# Main.net
KiCad netlist of a schematic drawn in Altium Designer
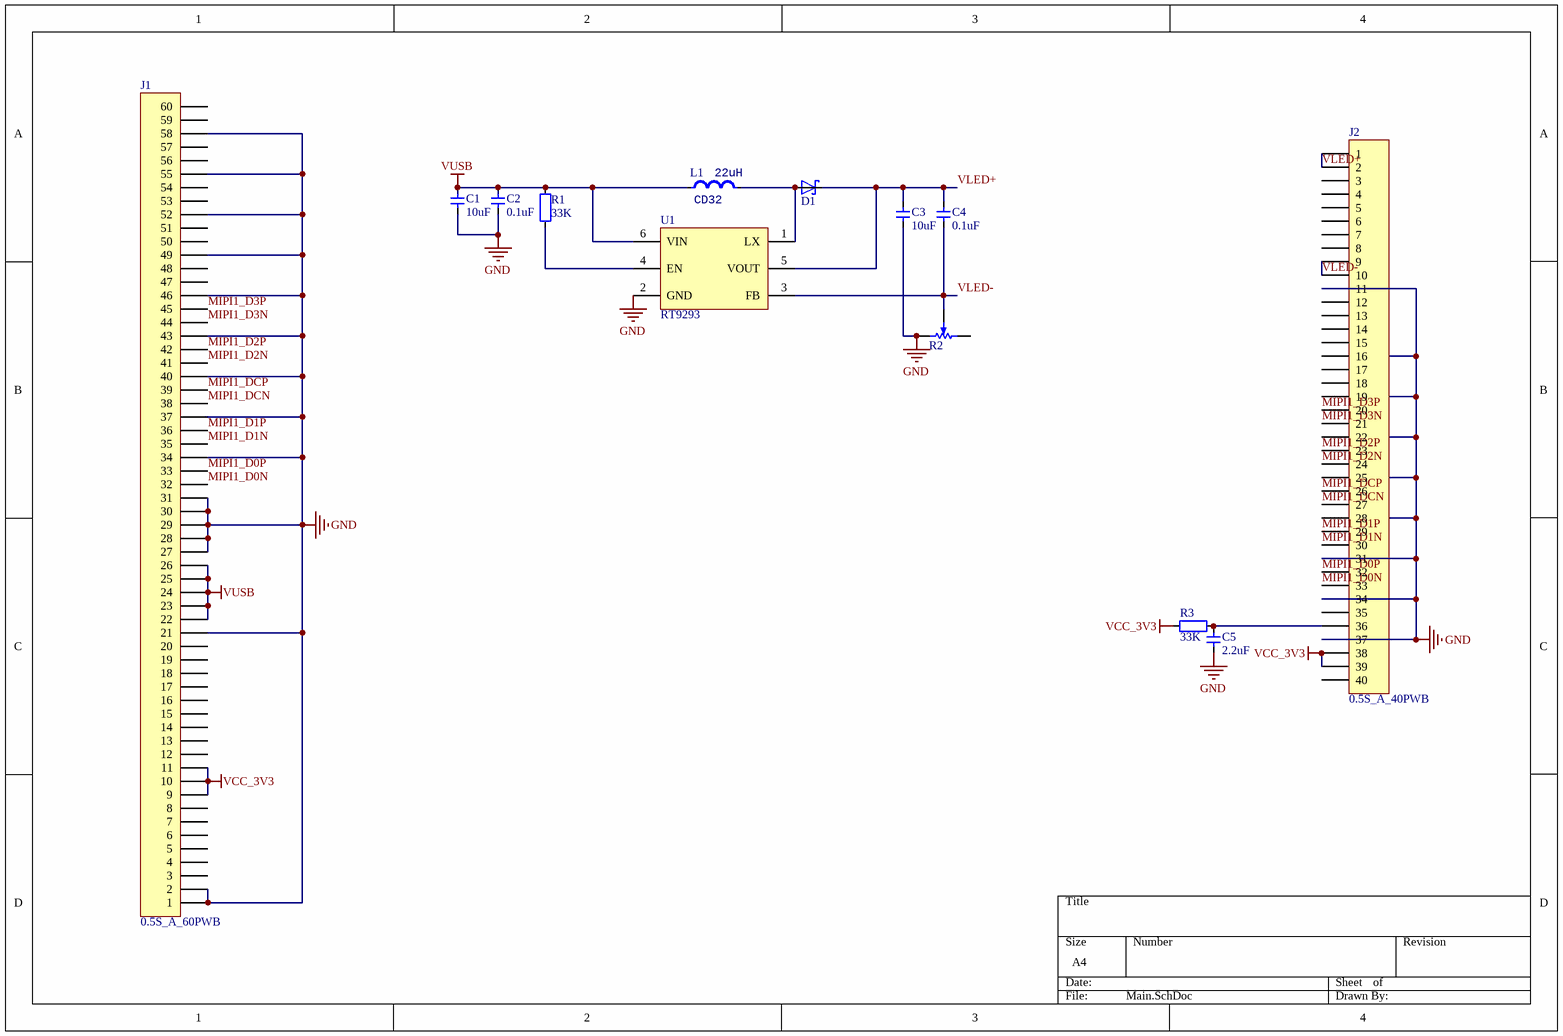
[diagram p0: Main.SchDoc]

(export (version "E")
  (design (tool "Eeschema 10.0.6"))
  (components
    (comp (ref "C1")
      (value "10uF")
      (footprint "CAP_0402")
      (description "Capacitor")
      (libsource (lib "MyPcbLib") (part "电容-0402"))
    )
    (comp (ref "C2")
      (value "0.1uF")
      (footprint "CAP_0402")
      (description "Capacitor")
      (libsource (lib "MyPcbLib") (part "电容-0402"))
    )
    (comp (ref "C3")
      (value "10uF")
      (footprint "CAP_0402")
      (description "Capacitor")
      (libsource (lib "MyPcbLib") (part "电容-0402"))
    )
    (comp (ref "C4")
      (value "0.1uF")
      (footprint "CAP_0402")
      (description "Capacitor")
      (libsource (lib "MyPcbLib") (part "电容-0402"))
    )
    (comp (ref "C5")
      (value "2.2uF")
      (footprint "CAP_0402")
      (description "Capacitor")
      (libsource (lib "MyPcbLib") (part "电容-0402"))
    )
    (comp (ref "D1")
      (value "RSX501L-20")
      (footprint "mLib:DO-214")
      (description "Diode Schottky 40V 1A Surface Mount SMA _DO-214AC_")
      (fields (field (name "MP") "SS14") (field (name "MF") "ON Semiconductor"))
      (libsource (lib "mLib") (part "RSX501L-20"))
    )
    (comp (ref "J1")
      (value "0.5S_A_60PWB")
      (footprint "FFC_0.5_60")
      (description "Header, 60-Pin")
      (fields (field (name "PUBLISHER") "Altium Limited"))
      (libsource (lib "mLib") (part "FPC60-0.5mm"))
    )
    (comp (ref "J2")
      (value "0.5S_A_40PWB")
      (footprint "FFC_0.5_40")
      (description "Header, 40-Pin")
      (fields (field (name "PUBLISHER") "Altium Limited"))
      (libsource (lib "MyPcbLib") (part "FPC40-0.5mm"))
    )
    (comp (ref "L1")
      (value "22uH")
      (footprint "IND_CD32")
      (description "Inductor")
      (fields (field (name "TYPE") "CD32") (field (name "Comment") "CD32"))
      (libsource (lib "KitSprout") (part "Ind_CD32"))
    )
    (comp (ref "R1")
      (value "33K")
      (footprint "RES_0402")
      (description "Resistor")
      (libsource (lib "MyPcbLib") (part "电阻-0402"))
    )
    (comp (ref "R2")
      (value "电位器-贴片")
      (footprint "贴片电位器 3*3")
      (fields (field (name "PUBLISHER") "Altium Limited"))
      (libsource (lib "MyPcbLib") (part "电位器-贴片"))
    )
    (comp (ref "R3")
      (value "33K")
      (footprint "RES_0402")
      (description "Resistor")
      (libsource (lib "") (part "电阻-0402_1"))
    )
    (comp (ref "U1")
      (value "RT9293")
      (footprint "SOT23-6")
      (description "LCD-LED Driver")
      (libsource (lib "mLib") (part "RT9293"))
    )
  )
  (nets
    (net (code "1") (name "/MIPI1_D0N") (class "Default")
      (node (ref "J1") (pin "32") (pinfunction "32_32") (pintype "passive"))
      (node (ref "J2") (pin "33") (pinfunction "33_33") (pintype "passive"))
    )
    (net (code "2") (name "/MIPI1_D0P") (class "Default")
      (node (ref "J1") (pin "33") (pinfunction "33_33") (pintype "passive"))
      (node (ref "J2") (pin "32") (pinfunction "32_32") (pintype "passive"))
    )
    (net (code "3") (name "/MIPI1_D1N") (class "Default")
      (node (ref "J1") (pin "35") (pinfunction "35_35") (pintype "passive"))
      (node (ref "J2") (pin "30") (pinfunction "30_30") (pintype "passive"))
    )
    (net (code "4") (name "/MIPI1_D1P") (class "Default")
      (node (ref "J1") (pin "36") (pinfunction "36_36") (pintype "passive"))
      (node (ref "J2") (pin "29") (pinfunction "29_29") (pintype "passive"))
    )
    (net (code "5") (name "/MIPI1_D2N") (class "Default")
      (node (ref "J1") (pin "41") (pinfunction "41_41") (pintype "passive"))
      (node (ref "J2") (pin "24") (pinfunction "24_24") (pintype "passive"))
    )
    (net (code "6") (name "/MIPI1_D2P") (class "Default")
      (node (ref "J1") (pin "42") (pinfunction "42_42") (pintype "passive"))
      (node (ref "J2") (pin "23") (pinfunction "23_23") (pintype "passive"))
    )
    (net (code "7") (name "/MIPI1_D3N") (class "Default")
      (node (ref "J1") (pin "44") (pinfunction "44_44") (pintype "passive"))
      (node (ref "J2") (pin "21") (pinfunction "21_21") (pintype "passive"))
    )
    (net (code "8") (name "/MIPI1_D3P") (class "Default")
      (node (ref "J1") (pin "45") (pinfunction "45_45") (pintype "passive"))
      (node (ref "J2") (pin "20") (pinfunction "20_20") (pintype "passive"))
    )
    (net (code "9") (name "/MIPI1_DCN") (class "Default")
      (node (ref "J1") (pin "38") (pinfunction "38_38") (pintype "passive"))
      (node (ref "J2") (pin "27") (pinfunction "27_27") (pintype "passive"))
    )
    (net (code "10") (name "/MIPI1_DCP") (class "Default")
      (node (ref "J1") (pin "39") (pinfunction "39_39") (pintype "passive"))
      (node (ref "J2") (pin "26") (pinfunction "26_26") (pintype "passive"))
    )
    (net (code "11") (name "/VLED+") (class "Default")
      (node (ref "C3") (pin "2") (pinfunction "2_2") (pintype "passive"))
      (node (ref "C4") (pin "2") (pinfunction "2_2") (pintype "passive"))
      (node (ref "D1") (pin "1") (pinfunction "1_1") (pintype "passive"))
      (node (ref "J2") (pin "1") (pinfunction "1_1") (pintype "passive"))
      (node (ref "J2") (pin "2") (pinfunction "2_2") (pintype "passive"))
      (node (ref "U1") (pin "5") (pinfunction "VOUT_5") (pintype "passive"))
    )
    (net (code "12") (name "/VLED-") (class "Default")
      (node (ref "C4") (pin "1") (pinfunction "1_1") (pintype "passive"))
      (node (ref "J2") (pin "10") (pinfunction "10_10") (pintype "passive"))
      (node (ref "J2") (pin "9") (pinfunction "9_9") (pintype "passive"))
      (node (ref "R2") (pin "3") (pinfunction "W_3") (pintype "passive"))
      (node (ref "U1") (pin "3") (pinfunction "FB_3") (pintype "passive"))
    )
    (net (code "13") (name "GND") (class "Default")
      (node (ref "C1") (pin "1") (pinfunction "1_1") (pintype "passive"))
      (node (ref "C2") (pin "1") (pinfunction "1_1") (pintype "passive"))
      (node (ref "C3") (pin "1") (pinfunction "1_1") (pintype "passive"))
      (node (ref "C5") (pin "2") (pinfunction "2_2") (pintype "passive"))
      (node (ref "J1") (pin "1") (pinfunction "1_1") (pintype "passive"))
      (node (ref "J1") (pin "2") (pinfunction "2_2") (pintype "passive"))
      (node (ref "J1") (pin "21") (pinfunction "21_21") (pintype "passive"))
      (node (ref "J1") (pin "27") (pinfunction "27_27") (pintype "passive"))
      (node (ref "J1") (pin "28") (pinfunction "28_28") (pintype "passive"))
      (node (ref "J1") (pin "29") (pinfunction "29_29") (pintype "passive"))
      (node (ref "J1") (pin "30") (pinfunction "30_30") (pintype "passive"))
      (node (ref "J1") (pin "31") (pinfunction "31_31") (pintype "passive"))
      (node (ref "J1") (pin "34") (pinfunction "34_34") (pintype "passive"))
      (node (ref "J1") (pin "37") (pinfunction "37_37") (pintype "passive"))
      (node (ref "J1") (pin "40") (pinfunction "40_40") (pintype "passive"))
      (node (ref "J1") (pin "43") (pinfunction "43_43") (pintype "passive"))
      (node (ref "J1") (pin "46") (pinfunction "46_46") (pintype "passive"))
      (node (ref "J1") (pin "49") (pinfunction "49_49") (pintype "passive"))
      (node (ref "J1") (pin "52") (pinfunction "52_52") (pintype "passive"))
      (node (ref "J1") (pin "55") (pinfunction "55_55") (pintype "passive"))
      (node (ref "J1") (pin "58") (pinfunction "58_58") (pintype "passive"))
      (node (ref "J2") (pin "11") (pinfunction "11_11") (pintype "passive"))
      (node (ref "J2") (pin "16") (pinfunction "16_16") (pintype "passive"))
      (node (ref "J2") (pin "19") (pinfunction "19_19") (pintype "passive"))
      (node (ref "J2") (pin "22") (pinfunction "22_22") (pintype "passive"))
      (node (ref "J2") (pin "25") (pinfunction "25_25") (pintype "passive"))
      (node (ref "J2") (pin "28") (pinfunction "28_28") (pintype "passive"))
      (node (ref "J2") (pin "31") (pinfunction "31_31") (pintype "passive"))
      (node (ref "J2") (pin "34") (pinfunction "34_34") (pintype "passive"))
      (node (ref "J2") (pin "37") (pinfunction "37_37") (pintype "passive"))
      (node (ref "R2") (pin "1") (pinfunction "+_1") (pintype "passive"))
      (node (ref "U1") (pin "2") (pinfunction "GND_2") (pintype "passive"))
    )
    (net (code "14") (name "Net-(C5-Pad1)") (class "Default")
      (node (ref "C5") (pin "1") (pinfunction "1_1") (pintype "passive"))
      (node (ref "J2") (pin "36") (pinfunction "36_36") (pintype "passive"))
      (node (ref "R3") (pin "1") (pinfunction "1_1") (pintype "passive"))
    )
    (net (code "15") (name "Net-(U1-EN)") (class "Default")
      (node (ref "R1") (pin "1") (pinfunction "1_1") (pintype "passive"))
      (node (ref "U1") (pin "4") (pinfunction "EN_4") (pintype "passive"))
    )
    (net (code "16") (name "Net-(U1-LX)") (class "Default")
      (node (ref "D1") (pin "2") (pinfunction "2_2") (pintype "passive"))
      (node (ref "L1") (pin "2") (pinfunction "2_2") (pintype "passive"))
      (node (ref "U1") (pin "1") (pinfunction "LX_1") (pintype "passive"))
    )
    (net (code "17") (name "VCC_3V3") (class "Default")
      (node (ref "J1") (pin "10") (pinfunction "10_10") (pintype "passive"))
      (node (ref "J1") (pin "11") (pinfunction "11_11") (pintype "passive"))
      (node (ref "J1") (pin "9") (pinfunction "9_9") (pintype "passive"))
      (node (ref "J2") (pin "38") (pinfunction "38_38") (pintype "passive"))
      (node (ref "J2") (pin "39") (pinfunction "39_39") (pintype "passive"))
      (node (ref "R3") (pin "2") (pinfunction "2_2") (pintype "passive"))
    )
    (net (code "18") (name "VUSB") (class "Default")
      (node (ref "C1") (pin "2") (pinfunction "2_2") (pintype "passive"))
      (node (ref "C2") (pin "2") (pinfunction "2_2") (pintype "passive"))
      (node (ref "J1") (pin "22") (pinfunction "22_22") (pintype "passive"))
      (node (ref "J1") (pin "23") (pinfunction "23_23") (pintype "passive"))
      (node (ref "J1") (pin "24") (pinfunction "24_24") (pintype "passive"))
      (node (ref "J1") (pin "25") (pinfunction "25_25") (pintype "passive"))
      (node (ref "J1") (pin "26") (pinfunction "26_26") (pintype "passive"))
      (node (ref "L1") (pin "1") (pinfunction "1_1") (pintype "passive"))
      (node (ref "R1") (pin "2") (pinfunction "2_2") (pintype "passive"))
      (node (ref "U1") (pin "6") (pinfunction "VIN_6") (pintype "passive"))
    )
    (net (code "19") (name "unconnected-(J1-Pad3)") (class "Default")
      (node (ref "J1") (pin "3") (pinfunction "3_3") (pintype "passive"))
    )
    (net (code "20") (name "unconnected-(J1-Pad4)") (class "Default")
      (node (ref "J1") (pin "4") (pinfunction "4_4") (pintype "passive"))
    )
    (net (code "21") (name "unconnected-(J1-Pad5)") (class "Default")
      (node (ref "J1") (pin "5") (pinfunction "5_5") (pintype "passive"))
    )
    (net (code "22") (name "unconnected-(J1-Pad6)") (class "Default")
      (node (ref "J1") (pin "6") (pinfunction "6_6") (pintype "passive"))
    )
    (net (code "23") (name "unconnected-(J1-Pad7)") (class "Default")
      (node (ref "J1") (pin "7") (pinfunction "7_7") (pintype "passive"))
    )
    (net (code "24") (name "unconnected-(J1-Pad8)") (class "Default")
      (node (ref "J1") (pin "8") (pinfunction "8_8") (pintype "passive"))
    )
    (net (code "25") (name "unconnected-(J1-Pad12)") (class "Default")
      (node (ref "J1") (pin "12") (pinfunction "12_12") (pintype "passive"))
    )
    (net (code "26") (name "unconnected-(J1-Pad13)") (class "Default")
      (node (ref "J1") (pin "13") (pinfunction "13_13") (pintype "passive"))
    )
    (net (code "27") (name "unconnected-(J1-Pad14)") (class "Default")
      (node (ref "J1") (pin "14") (pinfunction "14_14") (pintype "passive"))
    )
    (net (code "28") (name "unconnected-(J1-Pad15)") (class "Default")
      (node (ref "J1") (pin "15") (pinfunction "15_15") (pintype "passive"))
    )
    (net (code "29") (name "unconnected-(J1-Pad16)") (class "Default")
      (node (ref "J1") (pin "16") (pinfunction "16_16") (pintype "passive"))
    )
    (net (code "30") (name "unconnected-(J1-Pad17)") (class "Default")
      (node (ref "J1") (pin "17") (pinfunction "17_17") (pintype "passive"))
    )
    (net (code "31") (name "unconnected-(J1-Pad18)") (class "Default")
      (node (ref "J1") (pin "18") (pinfunction "18_18") (pintype "passive"))
    )
    (net (code "32") (name "unconnected-(J1-Pad19)") (class "Default")
      (node (ref "J1") (pin "19") (pinfunction "19_19") (pintype "passive"))
    )
    (net (code "33") (name "unconnected-(J1-Pad20)") (class "Default")
      (node (ref "J1") (pin "20") (pinfunction "20_20") (pintype "passive"))
    )
    (net (code "34") (name "unconnected-(J1-Pad47)") (class "Default")
      (node (ref "J1") (pin "47") (pinfunction "47_47") (pintype "passive"))
    )
    (net (code "35") (name "unconnected-(J1-Pad48)") (class "Default")
      (node (ref "J1") (pin "48") (pinfunction "48_48") (pintype "passive"))
    )
    (net (code "36") (name "unconnected-(J1-Pad50)") (class "Default")
      (node (ref "J1") (pin "50") (pinfunction "50_50") (pintype "passive"))
    )
    (net (code "37") (name "unconnected-(J1-Pad51)") (class "Default")
      (node (ref "J1") (pin "51") (pinfunction "51_51") (pintype "passive"))
    )
    (net (code "38") (name "unconnected-(J1-Pad53)") (class "Default")
      (node (ref "J1") (pin "53") (pinfunction "53_53") (pintype "passive"))
    )
    (net (code "39") (name "unconnected-(J1-Pad54)") (class "Default")
      (node (ref "J1") (pin "54") (pinfunction "54_54") (pintype "passive"))
    )
    (net (code "40") (name "unconnected-(J1-Pad56)") (class "Default")
      (node (ref "J1") (pin "56") (pinfunction "56_56") (pintype "passive"))
    )
    (net (code "41") (name "unconnected-(J1-Pad57)") (class "Default")
      (node (ref "J1") (pin "57") (pinfunction "57_57") (pintype "passive"))
    )
    (net (code "42") (name "unconnected-(J1-Pad59)") (class "Default")
      (node (ref "J1") (pin "59") (pinfunction "59_59") (pintype "passive"))
    )
    (net (code "43") (name "unconnected-(J1-Pad60)") (class "Default")
      (node (ref "J1") (pin "60") (pinfunction "60_60") (pintype "passive"))
    )
    (net (code "44") (name "unconnected-(J2-Pad3)") (class "Default")
      (node (ref "J2") (pin "3") (pinfunction "3_3") (pintype "passive"))
    )
    (net (code "45") (name "unconnected-(J2-Pad4)") (class "Default")
      (node (ref "J2") (pin "4") (pinfunction "4_4") (pintype "passive"))
    )
    (net (code "46") (name "unconnected-(J2-Pad5)") (class "Default")
      (node (ref "J2") (pin "5") (pinfunction "5_5") (pintype "passive"))
    )
    (net (code "47") (name "unconnected-(J2-Pad6)") (class "Default")
      (node (ref "J2") (pin "6") (pinfunction "6_6") (pintype "passive"))
    )
    (net (code "48") (name "unconnected-(J2-Pad7)") (class "Default")
      (node (ref "J2") (pin "7") (pinfunction "7_7") (pintype "passive"))
    )
    (net (code "49") (name "unconnected-(J2-Pad8)") (class "Default")
      (node (ref "J2") (pin "8") (pinfunction "8_8") (pintype "passive"))
    )
    (net (code "50") (name "unconnected-(J2-Pad12)") (class "Default")
      (node (ref "J2") (pin "12") (pinfunction "12_12") (pintype "passive"))
    )
    (net (code "51") (name "unconnected-(J2-Pad13)") (class "Default")
      (node (ref "J2") (pin "13") (pinfunction "13_13") (pintype "passive"))
    )
    (net (code "52") (name "unconnected-(J2-Pad14)") (class "Default")
      (node (ref "J2") (pin "14") (pinfunction "14_14") (pintype "passive"))
    )
    (net (code "53") (name "unconnected-(J2-Pad15)") (class "Default")
      (node (ref "J2") (pin "15") (pinfunction "15_15") (pintype "passive"))
    )
    (net (code "54") (name "unconnected-(J2-Pad17)") (class "Default")
      (node (ref "J2") (pin "17") (pinfunction "17_17") (pintype "passive"))
    )
    (net (code "55") (name "unconnected-(J2-Pad18)") (class "Default")
      (node (ref "J2") (pin "18") (pinfunction "18_18") (pintype "passive"))
    )
    (net (code "56") (name "unconnected-(J2-Pad35)") (class "Default")
      (node (ref "J2") (pin "35") (pinfunction "35_35") (pintype "passive"))
    )
    (net (code "57") (name "unconnected-(J2-Pad40)") (class "Default")
      (node (ref "J2") (pin "40") (pinfunction "40_40") (pintype "passive"))
    )
    (net (code "58") (name "unconnected-(R2---Pad2)") (class "Default")
      (node (ref "R2") (pin "2") (pinfunction "-_2") (pintype "passive"))
    )
  )
)
